# 24_063_24_069_HEAT.net
KiCad netlist of a schematic drawn in Altium Designer
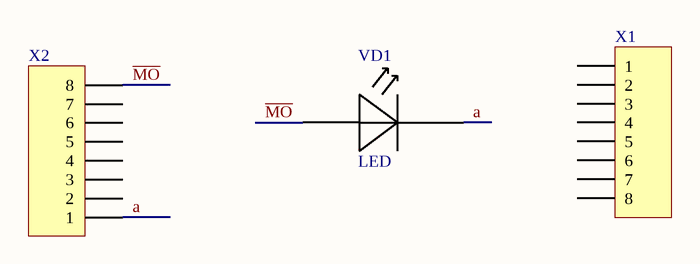
[diagram p0: 24.063_24.069_HEAT.SchDoc]

(export (version "E")
  (design (tool "Eeschema 10.0.6"))
  (components
    (comp (ref "VD1") (value "LED") (footprint "LED 24.063") (libsource (lib "msp_SchLib") (part "LED")))
    (comp (ref "X1")
      (value "Header 8")
      (footprint "HDR1X8")
      (description "Header, 8-Pin")
      (fields (field (name "PUBLISHER") "Altium Limited"))
      (libsource (lib "Miscellaneous Connectors") (part "Header 8"))
    )
    (comp (ref "X2")
      (value "Header 8")
      (footprint "HDR1X8")
      (description "Header, 8-Pin")
      (fields (field (name "PUBLISHER") "Altium Limited"))
      (libsource (lib "") (part "Header 8_1"))
    )
  )
  (nets
    (net (code "1") (name "/a") (class "Default")
      (node (ref "VD1") (pin "2") (pinfunction "2_2") (pintype "passive"))
      (node (ref "X2") (pin "1") (pinfunction "1_1") (pintype "passive"))
    )
    (net (code "2") (name "/~{MO}") (class "Default")
      (node (ref "VD1") (pin "1") (pinfunction "1_1") (pintype "passive"))
      (node (ref "X2") (pin "8") (pinfunction "8_8") (pintype "passive"))
    )
    (net (code "3") (name "unconnected-(X1-Pad1)") (class "Default")
      (node (ref "X1") (pin "1") (pinfunction "1_1") (pintype "passive"))
    )
    (net (code "4") (name "unconnected-(X1-Pad2)") (class "Default")
      (node (ref "X1") (pin "2") (pinfunction "2_2") (pintype "passive"))
    )
    (net (code "5") (name "unconnected-(X1-Pad3)") (class "Default")
      (node (ref "X1") (pin "3") (pinfunction "3_3") (pintype "passive"))
    )
    (net (code "6") (name "unconnected-(X1-Pad4)") (class "Default")
      (node (ref "X1") (pin "4") (pinfunction "4_4") (pintype "passive"))
    )
    (net (code "7") (name "unconnected-(X1-Pad5)") (class "Default")
      (node (ref "X1") (pin "5") (pinfunction "5_5") (pintype "passive"))
    )
    (net (code "8") (name "unconnected-(X1-Pad6)") (class "Default")
      (node (ref "X1") (pin "6") (pinfunction "6_6") (pintype "passive"))
    )
    (net (code "9") (name "unconnected-(X1-Pad7)") (class "Default")
      (node (ref "X1") (pin "7") (pinfunction "7_7") (pintype "passive"))
    )
    (net (code "10") (name "unconnected-(X1-Pad8)") (class "Default")
      (node (ref "X1") (pin "8") (pinfunction "8_8") (pintype "passive"))
    )
    (net (code "11") (name "unconnected-(X2-Pad2)") (class "Default")
      (node (ref "X2") (pin "2") (pinfunction "2_2") (pintype "passive"))
    )
    (net (code "12") (name "unconnected-(X2-Pad3)") (class "Default")
      (node (ref "X2") (pin "3") (pinfunction "3_3") (pintype "passive"))
    )
    (net (code "13") (name "unconnected-(X2-Pad4)") (class "Default")
      (node (ref "X2") (pin "4") (pinfunction "4_4") (pintype "passive"))
    )
    (net (code "14") (name "unconnected-(X2-Pad5)") (class "Default")
      (node (ref "X2") (pin "5") (pinfunction "5_5") (pintype "passive"))
    )
    (net (code "15") (name "unconnected-(X2-Pad6)") (class "Default")
      (node (ref "X2") (pin "6") (pinfunction "6_6") (pintype "passive"))
    )
    (net (code "16") (name "unconnected-(X2-Pad7)") (class "Default")
      (node (ref "X2") (pin "7") (pinfunction "7_7") (pintype "passive"))
    )
  )
)
